# Copy_of_ESP32.net
KiCad netlist of a schematic drawn in Altium Designer
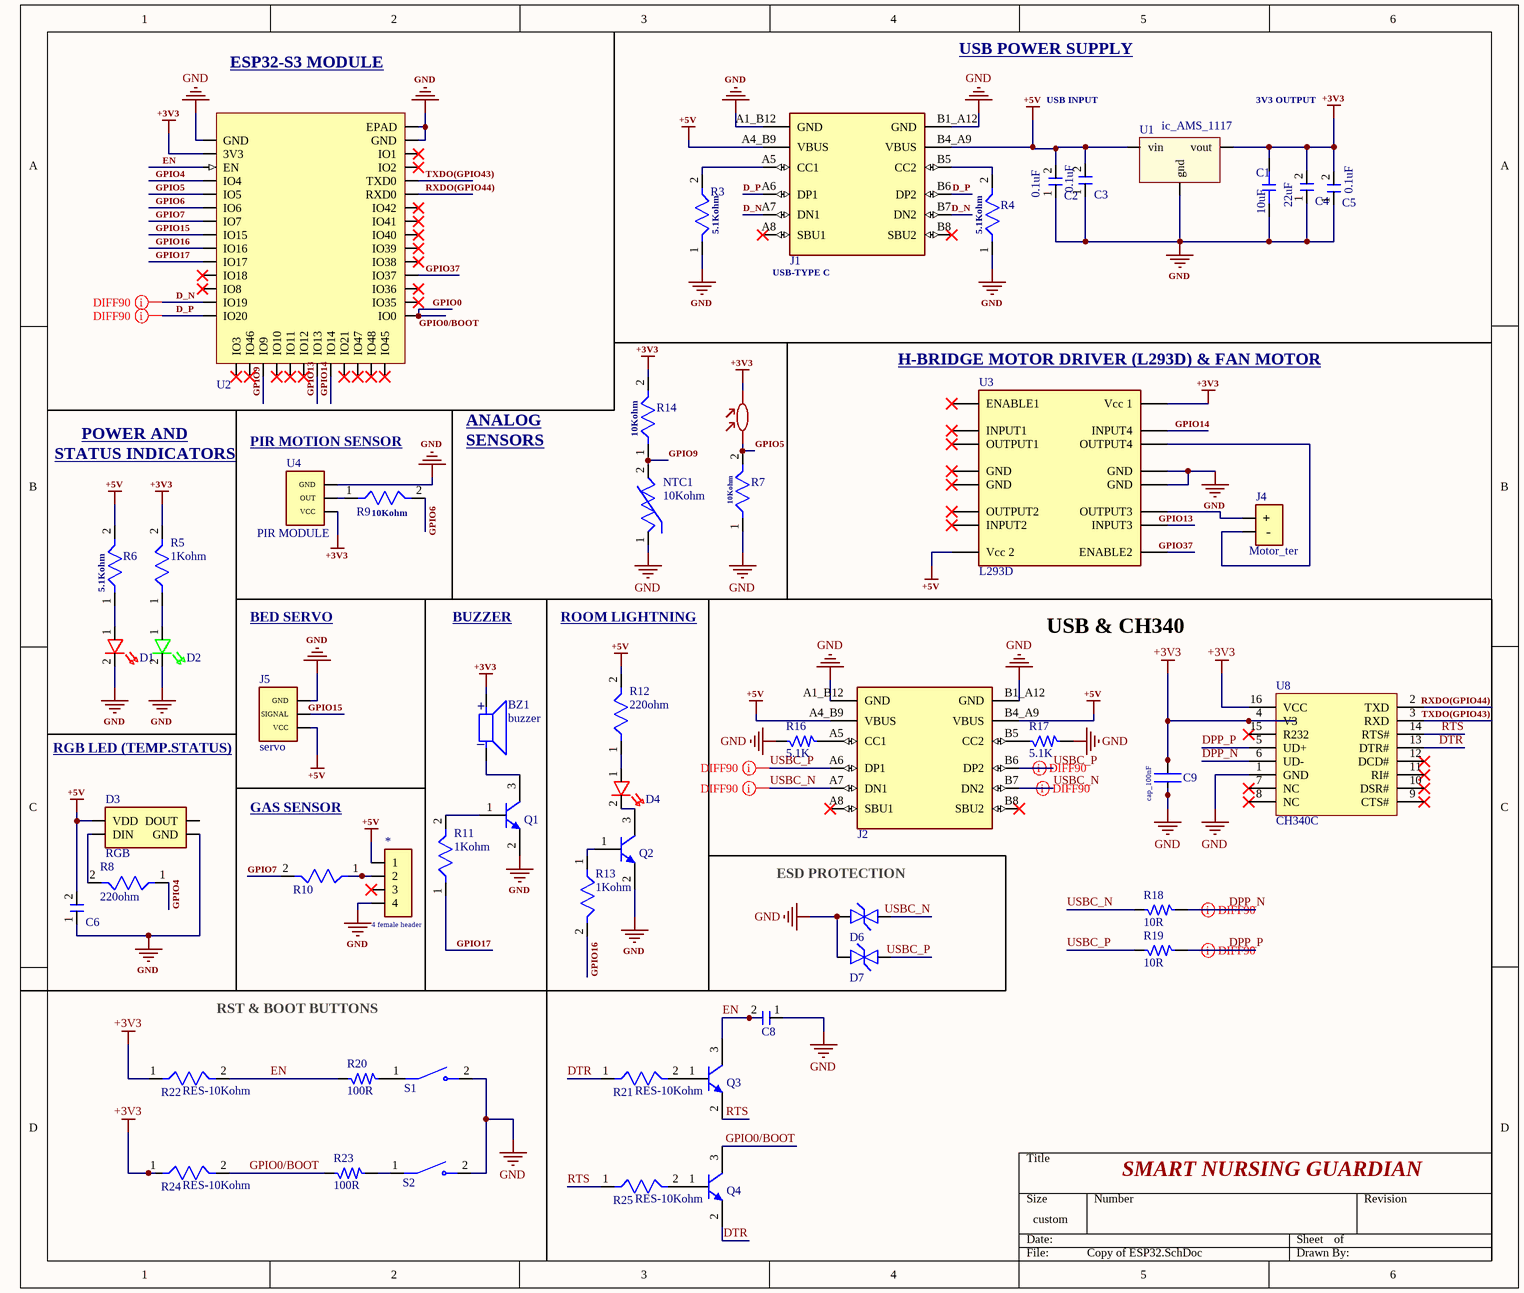
[diagram p0: Copy of ESP32.SchDoc]

(export (version "E")
  (design (tool "Eeschema 10.0.6"))
  (components
    (comp (ref "*")
      (value "4 female header")
      (footprint "4 female header")
      (description "CONN SOCKET 4POS 2.54mm SINGLE ROW TH")
      (fields (field (name "MFR") "BOOMELE(Boom Precision Elec)") (field (name "MPN") "2.54-1*4P"))
      (libsource (lib "mind") (part "4 female header"))
    )
    (comp (ref "BZ1")
      (value "buzzer")
      (footprint "buzzer")
      (description "BUZZER MAGNETIC 4V~8V 12mm TH")
      (fields (field (name "MFR") "Huaneng") (field (name "MPN") "TMB12A05"))
      (libsource (lib "ESP32") (part "buzzer"))
    )
    (comp (ref "C1")
      (value "10uF")
      (footprint "cap_0805")
      (fields (field (name "MFR") "Samsung Electro-Mechanics"))
      (libsource (lib "ESP32") (part "Cap_10uF"))
    )
    (comp (ref "C2")
      (value "0.1uF")
      (footprint "CAPC1608X50N")
      (description "CAP CER 100nF 50V X7R 0603")
      (libsource (lib "ESP32") (part "CAP-0.1uF"))
    )
    (comp (ref "C3")
      (value "0.1uF")
      (footprint "CAPC1608X50N")
      (description "CAP CER 100nF 50V X7R 0603")
      (libsource (lib "ESP32") (part "CAP-0.1uF"))
    )
    (comp (ref "C4")
      (value "22uF")
      (footprint "CAPC2012X125N")
      (description "CAP CER 22uF 25V X5R 0805")
      (libsource (lib "ESP32") (part "CAP-22uF"))
    )
    (comp (ref "C5")
      (value "0.1uF")
      (footprint "CAPC1608X50N")
      (description "CAP CER 100nF 50V X7R 0603")
      (libsource (lib "ESP32") (part "CAP-0.1uF"))
    )
    (comp (ref "C6")
      (value "CAP-0.1uF")
      (footprint "CAPC1608X50N")
      (description "CAP CER 100nF 50V X7R 0603")
      (libsource (lib "ESP32") (part "CAP-0.1uF"))
    )
    (comp (ref "C8")
      (value "CAP-0.1uF")
      (footprint "CAPC1608X50N")
      (description "CAP CER 100nF 50V X7R 0603")
      (libsource (lib "ESP32") (part "CAP-0.1uF"))
    )
    (comp (ref "C9")
      (value "cap_100nF")
      (footprint "CAPC100nf")
      (description "CAP CER 100nF 50V X7R 0805")
      (fields (field (name "MFR") "Samsung Electro-Mechanics") (field (name "MPN") "CL21B104KBCNNNC"))
      (libsource (lib "components") (part "cap_100nF"))
    )
    (comp (ref "D1")
      (value "RED LED")
      (footprint "RED LED")
      (description "LED RED 0603 SMD")
      (fields (field (name "MPN") "YLED0603B"))
      (libsource (lib "ESP32") (part "RED LED"))
    )
    (comp (ref "D2")
      (value "GREEN LED")
      (footprint "RED LED")
      (description "LED GREEN WATER CLEAR 0603 SMD")
      (fields (field (name "MPN") "PSC-1608U52GC-G4"))
      (libsource (lib "ESP32") (part "GREEN LED"))
    )
    (comp (ref "D3")
      (value "RGB")
      (footprint "RGB_LED")
      (fields
        (field (name "MFR") "Shenzhen LED Color Optoelectronic Inc.")
        (field (name "MPN") "SMD-4 Shenzhen LED Color Optoelectronic Inc.")
      )
      (libsource (lib "ESP32") (part "RGB"))
    )
    (comp (ref "D4")
      (value "RED LED")
      (footprint "RED LED")
      (description "LED RED 0603 SMD")
      (fields (field (name "MPN") "YLED0603B"))
      (libsource (lib "ESP32") (part "RED LED"))
    )
    (comp (ref "D6")
      (value "D_TVS_BI_0603")
      (footprint "D_0603")
      (description "Diode TVS / ESD Bidirectional 0603")
      (libsource (lib "components") (part "D_TVS_BI_0603"))
    )
    (comp (ref "D7")
      (value "D_TVS_BI_0603")
      (footprint "D_0603")
      (description "Diode TVS / ESD Bidirectional 0603")
      (fields
        (field (name "MANUFACTURER") "Nexperia")
        (field (name "MANUFACTURER PART NUMBER") "PTVS20VZ1USKYL")
      )
      (libsource (lib "components") (part "D_TVS_BI_0603"))
    )
    (comp (ref "J1")
      (value "USB-TYPE C")
      (footprint "Korean Hroparts Elec TYPE-C-31-M-12")
      (description "CONN RCPT Type-C 16POS SMD")
      (fields (field (name "MPN") "TYPE-C-31-M-12"))
      (libsource (lib "ESP32") (part "USB-TYPE C"))
    )
    (comp (ref "J2")
      (value "USB-TYPE C")
      (footprint "Korean Hroparts Elec TYPE-C-31-M-12")
      (description "CONN RCPT Type-C 16POS SMD")
      (fields (field (name "MPN") "TYPE-C-31-M-12"))
      (libsource (lib "ESP32") (part "USB-TYPE C"))
    )
    (comp (ref "J4")
      (value "Motor_ter")
      (footprint "motor_terminal")
      (description "TERM BLK 2POS 2.54mm TH")
      (fields (field (name "MFR") "Molex") (field (name "MPN") "397730002"))
      (libsource (lib "mind") (part "Motor_ter"))
    )
    (comp (ref "J5")
      (value "servo")
      (footprint "3 pin header 100 mils")
      (fields (field (name "MFR") "Harwin") (field (name "MPN") "M20-9990346"))
      (libsource (lib "ESP32") (part "FAN/DC MOTOR"))
    )
    (comp (ref "NTC1")
      (value "10Kohm")
      (footprint "THERM_NTCG203NH103JT1S")
      (description "10kΩ 440uA 3590K ±5% 200mW ±3% 0805 NTC Thermistors RoHS")
      (fields (field (name "MPN") "NTCG203NH103JT1S"))
      (libsource (lib "ESP32") (part "NTCG203NH103JT1S"))
    )
    (comp (ref "Q1")
      (value "MMSS8050-H-TP")
      (footprint "SOT 23-3")
      (description "Bipolar (BJT) Transistor NPN 25V 1.5A 100MHz 625mW Surface Mount SOT-23")
      (fields (field (name "MANUFACTURER") "MCC"))
      (libsource (lib "components") (part "TRNS-NPN_25V-1.5A-SOT23"))
    )
    (comp (ref "Q2")
      (value "MMSS8050-H-TP")
      (footprint "SOT 23-3")
      (description "Bipolar (BJT) Transistor NPN 25V 1.5A 100MHz 625mW Surface Mount SOT-23")
      (fields (field (name "MANUFACTURER") "MCC"))
      (libsource (lib "components") (part "TRNS-NPN_25V-1.5A-SOT23"))
    )
    (comp (ref "Q3")
      (value "MMSS8050-H-TP")
      (footprint "SOT 23-3")
      (description "Bipolar (BJT) Transistor NPN 25V 1.5A 100MHz 625mW Surface Mount SOT-23")
      (fields (field (name "MANUFACTURER") "MCC"))
      (libsource (lib "components") (part "TRNS-NPN_25V-1.5A-SOT23"))
    )
    (comp (ref "Q4")
      (value "MMSS8050-H-TP")
      (footprint "SOT 23-3")
      (description "Bipolar (BJT) Transistor NPN 25V 1.5A 100MHz 625mW Surface Mount SOT-23")
      (fields (field (name "MANUFACTURER") "MCC"))
      (libsource (lib "components") (part "TRNS-NPN_25V-1.5A-SOT23"))
    )
    (comp (ref "R3")
      (value "5.1Kohm")
      (footprint "RES")
      (description "RES 5.1kΩ ±1% 100mW 0603")
      (libsource (lib "") (part "RES-5.1Kohm_1"))
    )
    (comp (ref "R4")
      (value "5.1Kohm")
      (footprint "RES")
      (description "RES 5.1kΩ ±1% 100mW 0603")
      (libsource (lib "ESP32") (part "RES-5.1Kohm"))
    )
    (comp (ref "R5")
      (value "1Kohm")
      (footprint "RES")
      (description "RES 1kΩ ±1% 100mW 0603")
      (fields (field (name "MPN") "FRC0603F1001TS"))
      (libsource (lib "ESP32") (part "RES_1Kohm"))
    )
    (comp (ref "R6")
      (value "5.1Kohm")
      (footprint "RES")
      (description "RES 5.1kΩ ±1% 100mW 0603")
      (libsource (lib "ESP32") (part "RES-5.1Kohm"))
    )
    (comp (ref "R7")
      (value "10Kohm")
      (footprint "RES")
      (description "RES 10kΩ ±1% 100mW 0603")
      (libsource (lib "ESP32") (part "RES-10Kohm"))
    )
    (comp (ref "R8")
      (value "220ohm")
      (footprint "RES")
      (description "RES 220Ω ±1% 100mW 0603")
      (fields (field (name "MPN") "0603WAF2200T5E"))
      (libsource (lib "ESP32") (part "RES_220ohm"))
    )
    (comp (ref "R9")
      (value "10Kohm")
      (footprint "RES")
      (description "RES 10kΩ ±1% 100mW 0603")
      (libsource (lib "ESP32") (part "RES-10Kohm"))
    )
    (comp (ref "R10")
      (value "RES-10Kohm")
      (footprint "RES")
      (description "RES 10kΩ ±1% 100mW 0603")
      (libsource (lib "ESP32") (part "RES-10Kohm"))
    )
    (comp (ref "R11")
      (value "1Kohm")
      (footprint "RES")
      (description "RES 1kΩ ±1% 100mW 0603")
      (fields (field (name "MPN") "FRC0603F1001TS"))
      (libsource (lib "ESP32") (part "RES_1Kohm"))
    )
    (comp (ref "R12")
      (value "220ohm")
      (footprint "RES")
      (description "RES 220Ω ±1% 100mW 0603")
      (fields (field (name "MPN") "0603WAF2200T5E"))
      (libsource (lib "ESP32") (part "RES_220ohm"))
    )
    (comp (ref "R13")
      (value "1Kohm")
      (footprint "RES")
      (description "RES 1kΩ ±1% 100mW 0603")
      (fields (field (name "MPN") "FRC0603F1001TS"))
      (libsource (lib "ESP32") (part "RES_1Kohm"))
    )
    (comp (ref "R14")
      (value "10Kohm")
      (footprint "RES")
      (description "RES 10kΩ ±1% 100mW 0603")
      (libsource (lib "ESP32") (part "RES-10Kohm"))
    )
    (comp (ref "R15")
      (value "gl5539")
      (footprint "XDCR_PDV-P8003")
      (fields (field (name "MANUFACTURER") "森霸") (field (name "MANUFACTURERPART") "GL5539"))
      (libsource (lib "ESP32") (part "gl5539"))
    )
    (comp (ref "R16")
      (value "5.1K")
      (footprint "RES_0603")
      (description "4.7 kOhms ±1% 0.1W, 1/10W Chip Resistor 0603 (1608 Metric) Moisture Resistant Thick Film")
      (fields (field (name "MANUFACTURER") "Walsin") (field (name "MANUFACTURER PART NUMBER") "WR06X4701FTL"))
      (libsource (lib "components") (part "RES_4.7K-0.1W-1%-0603"))
    )
    (comp (ref "R17")
      (value "5.1K")
      (footprint "RES_0603")
      (description "4.7 kOhms ±1% 0.1W, 1/10W Chip Resistor 0603 (1608 Metric) Moisture Resistant Thick Film")
      (fields (field (name "MANUFACTURER") "Walsin") (field (name "MANUFACTURER PART NUMBER") "WR06X4701FTL"))
      (libsource (lib "components") (part "RES_4.7K-0.1W-1%-0603"))
    )
    (comp (ref "R18")
      (value "10R")
      (footprint "RES_0603")
      (fields (field (name "MANUFACTURER") "Walsin") (field (name "MANUFACTURER PART NUMBER") "WR06X10R0FTL"))
      (libsource (lib "components") (part "RES_10R-0.1W-1%-0603"))
    )
    (comp (ref "R19")
      (value "10R")
      (footprint "RES_0603")
      (fields (field (name "MANUFACTURER") "Walsin") (field (name "MANUFACTURER PART NUMBER") "WR06X10R0FTL"))
      (libsource (lib "components") (part "RES_10R-0.1W-1%-0603"))
    )
    (comp (ref "R20")
      (value "100R")
      (footprint "RES_0603")
      (description "100 Ohms ±1% 0.1W, 1/10W Chip Resistor 0603 (1608 Metric) Thick Film")
      (fields (field (name "MANUFACTURER") "Walsin") (field (name "MANUFACTURER PART NUMBER") "WR06X1000FTL"))
      (libsource (lib "components") (part "RES_100R-0.1W-1%-0603"))
    )
    (comp (ref "R21")
      (value "RES-10Kohm")
      (footprint "RES")
      (description "RES 10kΩ ±1% 100mW 0603")
      (libsource (lib "ESP32") (part "RES-10Kohm"))
    )
    (comp (ref "R22")
      (value "RES-10Kohm")
      (footprint "RES")
      (description "RES 10kΩ ±1% 100mW 0603")
      (libsource (lib "ESP32") (part "RES-10Kohm"))
    )
    (comp (ref "R23")
      (value "100R")
      (footprint "RES_0603")
      (description "100 Ohms ±1% 0.1W, 1/10W Chip Resistor 0603 (1608 Metric) Thick Film")
      (fields (field (name "MANUFACTURER") "Walsin") (field (name "MANUFACTURER PART NUMBER") "WR06X1000FTL"))
      (libsource (lib "components") (part "RES_100R-0.1W-1%-0603"))
    )
    (comp (ref "R24")
      (value "RES-10Kohm")
      (footprint "RES")
      (description "RES 10kΩ ±1% 100mW 0603")
      (libsource (lib "ESP32") (part "RES-10Kohm"))
    )
    (comp (ref "R25")
      (value "RES-10Kohm")
      (footprint "RES")
      (description "RES 10kΩ ±1% 100mW 0603")
      (libsource (lib "ESP32") (part "RES-10Kohm"))
    )
    (comp (ref "S1")
      (value "XUNPU TS-1088-AR02016")
      (footprint "XUNPU TS-1088-AR02016")
      (description "SWITCH TACTILE SPST 160gf SMD")
      (fields (field (name "MPN") "TS-1088-AR02016"))
      (libsource (lib "ESP32") (part "XUNPU TS-1088-AR02016"))
    )
    (comp (ref "S2")
      (value "XUNPU TS-1088-AR02016")
      (footprint "XUNPU TS-1088-AR02016")
      (description "SWITCH TACTILE SPST 160gf SMD")
      (fields (field (name "MPN") "TS-1088-AR02016"))
      (libsource (lib "ESP32") (part "XUNPU TS-1088-AR02016"))
    )
    (comp (ref "U1")
      (value "ic_AMS_1117")
      (footprint "ams1117 ic")
      (description "1A Low Dropout (LDO) Regulator")
      (fields (field (name "MFR") "Advanced Monolithic Systems") (field (name "MFR PART #") "AMS1117-3.3"))
      (libsource (lib "components") (part "ic_AMS_1117"))
    )
    (comp (ref "U2")
      (value "ESP32-S3-WROOM-1")
      (footprint "ESP32-S3-WROOM-1")
      (description "2.4 GHz Wi-Fi + Bluetooth + Bluetooth LE module")
      (libsource (lib "ESP32") (part "ESP32-S3-WROOM-1"))
    )
    (comp (ref "U3")
      (value "L293D")
      (footprint "l293D")
      (description "Bipolar Motor Driver - Parallel 16-PowerDIP")
      (fields (field (name "MFR") "ST") (field (name "SUP PART #") "C12340"))
      (libsource (lib "ESP32") (part "L293D"))
    )
    (comp (ref "U4")
      (value "PIR MODULE")
      (footprint "3 pin header 100 mils")
      (fields (field (name "MFR") "Harwin") (field (name "MPN") "M20-9990346"))
      (libsource (lib "ESP32") (part "3 PIN HEADER 100mils pitch"))
    )
    (comp (ref "U8")
      (value "CH340C")
      (footprint "PCBComponent_1")
      (description "USB Bridge, USB to UART USB 2.0 UART Interface")
      (fields (field (name "MANUFACTURER") "Olimex"))
      (libsource (lib "components") (part "IC_CH340C"))
    )
  )
  (nets
    (net (code "1") (name "+3V3") (class "Default")
      (node (ref "BZ1") (pin "P") (pinfunction "P_P") (pintype "passive"))
      (node (ref "C1") (pin "2") (pinfunction "2_2") (pintype "passive"))
      (node (ref "C4") (pin "2") (pinfunction "2_2") (pintype "passive"))
      (node (ref "C5") (pin "2") (pinfunction "2_2") (pintype "passive"))
      (node (ref "C9") (pin "2") (pinfunction "2_2") (pintype "passive"))
      (node (ref "R14") (pin "2") (pinfunction "2_2") (pintype "passive"))
      (node (ref "R15") (pin "2") (pinfunction "2_2") (pintype "passive"))
      (node (ref "R22") (pin "1") (pinfunction "1_1") (pintype "passive"))
      (node (ref "R24") (pin "1") (pinfunction "1_1") (pintype "passive"))
      (node (ref "R5") (pin "2") (pinfunction "2_2") (pintype "passive"))
      (node (ref "U1") (pin "vout") (pinfunction "vout_vout") (pintype "passive"))
      (node (ref "U2") (pin "2") (pinfunction "3V3_2") (pintype "power_in"))
      (node (ref "U3") (pin "16") (pinfunction "Vcc_1_16") (pintype "power_in"))
      (node (ref "U4") (pin "1") (pinfunction "VCC_1") (pintype "passive"))
      (node (ref "U8") (pin "16") (pinfunction "VCC_16") (pintype "passive"))
      (node (ref "U8") (pin "4") (pinfunction "V3_4") (pintype "passive"))
    )
    (net (code "2") (name "+5V") (class "Default")
      (node (ref "*") (pin "1") (pinfunction "1_1") (pintype "passive"))
      (node (ref "C2") (pin "2") (pinfunction "2_2") (pintype "passive"))
      (node (ref "C3") (pin "2") (pinfunction "2_2") (pintype "passive"))
      (node (ref "C6") (pin "2") (pinfunction "2_2") (pintype "passive"))
      (node (ref "D3") (pin "1") (pinfunction "VDD_1") (pintype "power_in"))
      (node (ref "J1") (pin "A4_B9") (pinfunction "VBUS_A4_B9") (pintype "power_in"))
      (node (ref "J1") (pin "B4_A9") (pinfunction "VBUS_B4_A9") (pintype "power_in"))
      (node (ref "J2") (pin "A4_B9") (pinfunction "VBUS_A4_B9") (pintype "power_in"))
      (node (ref "J2") (pin "B4_A9") (pinfunction "VBUS_B4_A9") (pintype "power_in"))
      (node (ref "J5") (pin "1") (pinfunction "VCC_1") (pintype "passive"))
      (node (ref "R12") (pin "2") (pinfunction "2_2") (pintype "passive"))
      (node (ref "R6") (pin "2") (pinfunction "2_2") (pintype "passive"))
      (node (ref "U1") (pin "vin") (pinfunction "vin_vin") (pintype "passive"))
      (node (ref "U3") (pin "8") (pinfunction "Vcc_2_8") (pintype "power_in"))
    )
    (net (code "3") (name "/DPP_N") (class "Default")
      (node (ref "R18") (pin "2") (pinfunction "2_2") (pintype "passive"))
      (node (ref "U8") (pin "6") (pinfunction "UD-_6") (pintype "passive"))
    )
    (net (code "4") (name "/DPP_P") (class "Default")
      (node (ref "R19") (pin "2") (pinfunction "2_2") (pintype "passive"))
      (node (ref "U8") (pin "5") (pinfunction "UD+_5") (pintype "passive"))
    )
    (net (code "5") (name "/DTR") (class "Default")
      (node (ref "Q4") (pin "2") (pinfunction "E_2") (pintype "passive"))
      (node (ref "R21") (pin "1") (pinfunction "1_1") (pintype "passive"))
      (node (ref "U8") (pin "13") (pinfunction "DTR#_13") (pintype "passive"))
    )
    (net (code "6") (name "/D_N") (class "Default")
      (node (ref "J1") (pin "A7") (pinfunction "DN1_A7") (pintype "bidirectional"))
      (node (ref "J1") (pin "B7") (pinfunction "DN2_B7") (pintype "bidirectional"))
      (node (ref "U2") (pin "13") (pinfunction "IO19_13") (pintype "bidirectional"))
    )
    (net (code "7") (name "/D_P") (class "Default")
      (node (ref "J1") (pin "A6") (pinfunction "DP1_A6") (pintype "bidirectional"))
      (node (ref "J1") (pin "B6") (pinfunction "DP2_B6") (pintype "bidirectional"))
      (node (ref "U2") (pin "14") (pinfunction "IO20_14") (pintype "bidirectional"))
    )
    (net (code "8") (name "/EN") (class "Default")
      (node (ref "C8") (pin "2") (pinfunction "2_2") (pintype "passive"))
      (node (ref "Q3") (pin "3") (pinfunction "C_3") (pintype "passive"))
      (node (ref "R20") (pin "1") (pinfunction "1_1") (pintype "passive"))
      (node (ref "R22") (pin "2") (pinfunction "2_2") (pintype "passive"))
      (node (ref "U2") (pin "3") (pinfunction "EN_3") (pintype "input"))
    )
    (net (code "9") (name "/GPIO0") (class "Default")
      (node (ref "Q4") (pin "3") (pinfunction "C_3") (pintype "passive"))
      (node (ref "R23") (pin "1") (pinfunction "1_1") (pintype "passive"))
      (node (ref "R24") (pin "2") (pinfunction "2_2") (pintype "passive"))
      (node (ref "U2") (pin "27") (pinfunction "IO0_27") (pintype "bidirectional"))
    )
    (net (code "10") (name "/GPIO4") (class "Default")
      (node (ref "R8") (pin "1") (pinfunction "1_1") (pintype "passive"))
      (node (ref "U2") (pin "4") (pinfunction "IO4_4") (pintype "bidirectional"))
    )
    (net (code "11") (name "/GPIO5") (class "Default")
      (node (ref "R15") (pin "1") (pinfunction "1_1") (pintype "passive"))
      (node (ref "R7") (pin "2") (pinfunction "2_2") (pintype "passive"))
      (node (ref "U2") (pin "5") (pinfunction "IO5_5") (pintype "bidirectional"))
    )
    (net (code "12") (name "/GPIO6") (class "Default")
      (node (ref "R9") (pin "2") (pinfunction "2_2") (pintype "passive"))
      (node (ref "U2") (pin "6") (pinfunction "IO6_6") (pintype "bidirectional"))
    )
    (net (code "13") (name "/GPIO7") (class "Default")
      (node (ref "R10") (pin "2") (pinfunction "2_2") (pintype "passive"))
      (node (ref "U2") (pin "7") (pinfunction "IO7_7") (pintype "bidirectional"))
    )
    (net (code "14") (name "/GPIO9") (class "Default")
      (node (ref "NTC1") (pin "2") (pinfunction "2_2") (pintype "passive"))
      (node (ref "R14") (pin "1") (pinfunction "1_1") (pintype "passive"))
      (node (ref "U2") (pin "17") (pinfunction "IO9_17") (pintype "bidirectional"))
    )
    (net (code "15") (name "/GPIO13") (class "Default")
      (node (ref "U2") (pin "21") (pinfunction "IO13_21") (pintype "bidirectional"))
      (node (ref "U3") (pin "10") (pinfunction "INPUT3_10") (pintype "passive"))
    )
    (net (code "16") (name "/GPIO14") (class "Default")
      (node (ref "U2") (pin "22") (pinfunction "IO14_22") (pintype "bidirectional"))
      (node (ref "U3") (pin "15") (pinfunction "INPUT4_15") (pintype "passive"))
    )
    (net (code "17") (name "/GPIO15") (class "Default")
      (node (ref "J5") (pin "2") (pinfunction "SIGNAL_2") (pintype "passive"))
      (node (ref "U2") (pin "8") (pinfunction "IO15_8") (pintype "bidirectional"))
    )
    (net (code "18") (name "/GPIO16") (class "Default")
      (node (ref "R13") (pin "2") (pinfunction "2_2") (pintype "passive"))
      (node (ref "U2") (pin "9") (pinfunction "IO16_9") (pintype "bidirectional"))
    )
    (net (code "19") (name "/GPIO17") (class "Default")
      (node (ref "R11") (pin "1") (pinfunction "1_1") (pintype "passive"))
      (node (ref "U2") (pin "10") (pinfunction "IO17_10") (pintype "bidirectional"))
    )
    (net (code "20") (name "/GPIO37") (class "Default")
      (node (ref "U2") (pin "30") (pinfunction "IO37_30") (pintype "bidirectional"))
      (node (ref "U3") (pin "9") (pinfunction "ENABLE2_9") (pintype "passive"))
    )
    (net (code "21") (name "/RTS") (class "Default")
      (node (ref "Q3") (pin "2") (pinfunction "E_2") (pintype "passive"))
      (node (ref "R25") (pin "1") (pinfunction "1_1") (pintype "passive"))
      (node (ref "U8") (pin "14") (pinfunction "RTS#_14") (pintype "passive"))
    )
    (net (code "22") (name "/RXDO(GPIO44)") (class "Default")
      (node (ref "U2") (pin "36") (pinfunction "RXD0_36") (pintype "bidirectional"))
      (node (ref "U8") (pin "2") (pinfunction "TXD_2") (pintype "passive"))
    )
    (net (code "23") (name "/TXDO(GPIO43)") (class "Default")
      (node (ref "U2") (pin "37") (pinfunction "TXD0_37") (pintype "bidirectional"))
      (node (ref "U8") (pin "3") (pinfunction "RXD_3") (pintype "passive"))
    )
    (net (code "24") (name "/USBC_N") (class "Default")
      (node (ref "D6") (pin "K") (pinfunction "K_K") (pintype "passive"))
      (node (ref "J2") (pin "A7") (pinfunction "DN1_A7") (pintype "bidirectional"))
      (node (ref "J2") (pin "B7") (pinfunction "DN2_B7") (pintype "bidirectional"))
      (node (ref "R18") (pin "1") (pinfunction "1_1") (pintype "passive"))
    )
    (net (code "25") (name "/USBC_P") (class "Default")
      (node (ref "D7") (pin "K") (pinfunction "K_K") (pintype "passive"))
      (node (ref "J2") (pin "A6") (pinfunction "DP1_A6") (pintype "bidirectional"))
      (node (ref "J2") (pin "B6") (pinfunction "DP2_B6") (pintype "bidirectional"))
      (node (ref "R19") (pin "1") (pinfunction "1_1") (pintype "passive"))
    )
    (net (code "26") (name "GND") (class "Default")
      (node (ref "*") (pin "4") (pinfunction "4_4") (pintype "passive"))
      (node (ref "C1") (pin "1") (pinfunction "1_1") (pintype "passive"))
      (node (ref "C2") (pin "1") (pinfunction "1_1") (pintype "passive"))
      (node (ref "C3") (pin "1") (pinfunction "1_1") (pintype "passive"))
      (node (ref "C4") (pin "1") (pinfunction "1_1") (pintype "passive"))
      (node (ref "C5") (pin "1") (pinfunction "1_1") (pintype "passive"))
      (node (ref "C6") (pin "1") (pinfunction "1_1") (pintype "passive"))
      (node (ref "C8") (pin "1") (pinfunction "1_1") (pintype "passive"))
      (node (ref "C9") (pin "1") (pinfunction "1_1") (pintype "passive"))
      (node (ref "D1") (pin "2") (pinfunction "2_2") (pintype "passive"))
      (node (ref "D2") (pin "2") (pinfunction "2_2") (pintype "passive"))
      (node (ref "D3") (pin "3") (pinfunction "GND_3") (pintype "power_in"))
      (node (ref "D6") (pin "A") (pinfunction "A_A") (pintype "passive"))
      (node (ref "D7") (pin "A") (pinfunction "A_A") (pintype "passive"))
      (node (ref "J1") (pin "A1_B12") (pinfunction "GND_A1_B12") (pintype "power_in"))
      (node (ref "J1") (pin "B1_A12") (pinfunction "GND_B1_A12") (pintype "power_in"))
      (node (ref "J2") (pin "A1_B12") (pinfunction "GND_A1_B12") (pintype "power_in"))
      (node (ref "J2") (pin "B1_A12") (pinfunction "GND_B1_A12") (pintype "power_in"))
      (node (ref "J5") (pin "3") (pinfunction "GND_3") (pintype "passive"))
      (node (ref "NTC1") (pin "1") (pinfunction "1_1") (pintype "passive"))
      (node (ref "Q1") (pin "2") (pinfunction "E_2") (pintype "passive"))
      (node (ref "Q2") (pin "2") (pinfunction "E_2") (pintype "passive"))
      (node (ref "R16") (pin "1") (pinfunction "1_1") (pintype "passive"))
      (node (ref "R17") (pin "2") (pinfunction "2_2") (pintype "passive"))
      (node (ref "R3") (pin "1") (pinfunction "1_1") (pintype "passive"))
      (node (ref "R4") (pin "1") (pinfunction "1_1") (pintype "passive"))
      (node (ref "R7") (pin "1") (pinfunction "1_1") (pintype "passive"))
      (node (ref "S1") (pin "2") (pinfunction "2_2") (pintype "passive"))
      (node (ref "S2") (pin "2") (pinfunction "2_2") (pintype "passive"))
      (node (ref "U1") (pin "gnd") (pinfunction "gnd_gnd") (pintype "passive"))
      (node (ref "U2") (pin "1") (pinfunction "GND_1") (pintype "power_in"))
      (node (ref "U2") (pin "40") (pinfunction "GND_40") (pintype "power_in"))
      (node (ref "U2") (pin "41") (pinfunction "EPAD_41") (pintype "power_in"))
      (node (ref "U3") (pin "12") (pinfunction "GND_12") (pintype "power_in"))
      (node (ref "U3") (pin "13") (pinfunction "GND_13") (pintype "power_in"))
      (node (ref "U4") (pin "3") (pinfunction "GND_3") (pintype "passive"))
      (node (ref "U8") (pin "1") (pinfunction "GND_1") (pintype "passive"))
    )
    (net (code "27") (name "Net-(*-Pad2)") (class "Default")
      (node (ref "*") (pin "2") (pinfunction "2_2") (pintype "passive"))
      (node (ref "R10") (pin "1") (pinfunction "1_1") (pintype "passive"))
    )
    (net (code "28") (name "Net-(D1-Pad1)") (class "Default")
      (node (ref "D1") (pin "1") (pinfunction "1_1") (pintype "passive"))
      (node (ref "R6") (pin "1") (pinfunction "1_1") (pintype "passive"))
    )
    (net (code "29") (name "Net-(D2-Pad1)") (class "Default")
      (node (ref "D2") (pin "1") (pinfunction "1_1") (pintype "passive"))
      (node (ref "R5") (pin "1") (pinfunction "1_1") (pintype "passive"))
    )
    (net (code "30") (name "Net-(D3-DIN)") (class "Default")
      (node (ref "D3") (pin "2") (pinfunction "DIN_2") (pintype "passive"))
      (node (ref "R8") (pin "2") (pinfunction "2_2") (pintype "passive"))
    )
    (net (code "31") (name "Net-(D4-Pad1)") (class "Default")
      (node (ref "D4") (pin "1") (pinfunction "1_1") (pintype "passive"))
      (node (ref "R12") (pin "1") (pinfunction "1_1") (pintype "passive"))
    )
    (net (code "32") (name "Net-(J1-CC1)") (class "Default")
      (node (ref "J1") (pin "A5") (pinfunction "CC1_A5") (pintype "bidirectional"))
      (node (ref "R3") (pin "2") (pinfunction "2_2") (pintype "passive"))
    )
    (net (code "33") (name "Net-(J1-CC2)") (class "Default")
      (node (ref "J1") (pin "B5") (pinfunction "CC2_B5") (pintype "bidirectional"))
      (node (ref "R4") (pin "2") (pinfunction "2_2") (pintype "passive"))
    )
    (net (code "34") (name "Net-(J2-CC1)") (class "Default")
      (node (ref "J2") (pin "A5") (pinfunction "CC1_A5") (pintype "bidirectional"))
      (node (ref "R16") (pin "2") (pinfunction "2_2") (pintype "passive"))
    )
    (net (code "35") (name "Net-(J2-CC2)") (class "Default")
      (node (ref "J2") (pin "B5") (pinfunction "CC2_B5") (pintype "bidirectional"))
      (node (ref "R17") (pin "1") (pinfunction "1_1") (pintype "passive"))
    )
    (net (code "36") (name "Net-(J4-+)") (class "Default")
      (node (ref "J4") (pin "1") (pinfunction "+_1") (pintype "passive"))
      (node (ref "U3") (pin "11") (pinfunction "OUTPUT3_11") (pintype "passive"))
    )
    (net (code "37") (name "Net-(J4--)") (class "Default")
      (node (ref "J4") (pin "2") (pinfunction "-_2") (pintype "passive"))
      (node (ref "U3") (pin "14") (pinfunction "OUTPUT4_14") (pintype "passive"))
    )
    (net (code "38") (name "Net-(Q1-B)") (class "Default")
      (node (ref "Q1") (pin "1") (pinfunction "B_1") (pintype "passive"))
      (node (ref "R11") (pin "2") (pinfunction "2_2") (pintype "passive"))
    )
    (net (code "39") (name "Net-(Q1-C)") (class "Default")
      (node (ref "BZ1") (pin "N") (pinfunction "N_N") (pintype "passive"))
      (node (ref "Q1") (pin "3") (pinfunction "C_3") (pintype "passive"))
    )
    (net (code "40") (name "Net-(Q2-B)") (class "Default")
      (node (ref "Q2") (pin "1") (pinfunction "B_1") (pintype "passive"))
      (node (ref "R13") (pin "1") (pinfunction "1_1") (pintype "passive"))
    )
    (net (code "41") (name "Net-(Q2-C)") (class "Default")
      (node (ref "D4") (pin "2") (pinfunction "2_2") (pintype "passive"))
      (node (ref "Q2") (pin "3") (pinfunction "C_3") (pintype "passive"))
    )
    (net (code "42") (name "Net-(Q3-B)") (class "Default")
      (node (ref "Q3") (pin "1") (pinfunction "B_1") (pintype "passive"))
      (node (ref "R21") (pin "2") (pinfunction "2_2") (pintype "passive"))
    )
    (net (code "43") (name "Net-(Q4-B)") (class "Default")
      (node (ref "Q4") (pin "1") (pinfunction "B_1") (pintype "passive"))
      (node (ref "R25") (pin "2") (pinfunction "2_2") (pintype "passive"))
    )
    (net (code "44") (name "Net-(R20-Pad2)") (class "Default")
      (node (ref "R20") (pin "2") (pinfunction "2_2") (pintype "passive"))
      (node (ref "S1") (pin "1") (pinfunction "1_1") (pintype "passive"))
    )
    (net (code "45") (name "Net-(R23-Pad2)") (class "Default")
      (node (ref "R23") (pin "2") (pinfunction "2_2") (pintype "passive"))
      (node (ref "S2") (pin "1") (pinfunction "1_1") (pintype "passive"))
    )
    (net (code "46") (name "Net-(U4-OUT)") (class "Default")
      (node (ref "R9") (pin "1") (pinfunction "1_1") (pintype "passive"))
      (node (ref "U4") (pin "2") (pinfunction "OUT_2") (pintype "passive"))
    )
    (net (code "47") (name "unconnected-(*-Pad3)") (class "Default")
      (node (ref "*") (pin "3") (pinfunction "3_3") (pintype "passive+no_connect"))
    )
    (net (code "48") (name "unconnected-(D3-DOUT-Pad4)") (class "Default")
      (node (ref "D3") (pin "4") (pinfunction "DOUT_4") (pintype "passive"))
    )
    (net (code "49") (name "unconnected-(J1-SBU1-PadA8)") (class "Default")
      (node (ref "J1") (pin "A8") (pinfunction "SBU1_A8") (pintype "bidirectional+no_connect"))
    )
    (net (code "50") (name "unconnected-(J1-SBU2-PadB8)") (class "Default")
      (node (ref "J1") (pin "B8") (pinfunction "SBU2_B8") (pintype "bidirectional+no_connect"))
    )
    (net (code "51") (name "unconnected-(J2-SBU1-PadA8)") (class "Default")
      (node (ref "J2") (pin "A8") (pinfunction "SBU1_A8") (pintype "bidirectional+no_connect"))
    )
    (net (code "52") (name "unconnected-(J2-SBU2-PadB8)") (class "Default")
      (node (ref "J2") (pin "B8") (pinfunction "SBU2_B8") (pintype "bidirectional+no_connect"))
    )
    (net (code "53") (name "unconnected-(U2-IO1-Pad39)") (class "Default")
      (node (ref "U2") (pin "39") (pinfunction "IO1_39") (pintype "bidirectional+no_connect"))
    )
    (net (code "54") (name "unconnected-(U2-IO2-Pad38)") (class "Default")
      (node (ref "U2") (pin "38") (pinfunction "IO2_38") (pintype "bidirectional+no_connect"))
    )
    (net (code "55") (name "unconnected-(U2-IO3-Pad15)") (class "Default")
      (node (ref "U2") (pin "15") (pinfunction "IO3_15") (pintype "bidirectional+no_connect"))
    )
    (net (code "56") (name "unconnected-(U2-IO8-Pad12)") (class "Default")
      (node (ref "U2") (pin "12") (pinfunction "IO8_12") (pintype "bidirectional+no_connect"))
    )
    (net (code "57") (name "unconnected-(U2-IO10-Pad18)") (class "Default")
      (node (ref "U2") (pin "18") (pinfunction "IO10_18") (pintype "bidirectional+no_connect"))
    )
    (net (code "58") (name "unconnected-(U2-IO11-Pad19)") (class "Default")
      (node (ref "U2") (pin "19") (pinfunction "IO11_19") (pintype "bidirectional+no_connect"))
    )
    (net (code "59") (name "unconnected-(U2-IO12-Pad20)") (class "Default")
      (node (ref "U2") (pin "20") (pinfunction "IO12_20") (pintype "bidirectional+no_connect"))
    )
    (net (code "60") (name "unconnected-(U2-IO18-Pad11)") (class "Default")
      (node (ref "U2") (pin "11") (pinfunction "IO18_11") (pintype "bidirectional+no_connect"))
    )
    (net (code "61") (name "unconnected-(U2-IO21-Pad23)") (class "Default")
      (node (ref "U2") (pin "23") (pinfunction "IO21_23") (pintype "bidirectional+no_connect"))
    )
    (net (code "62") (name "unconnected-(U2-IO35-Pad28)") (class "Default")
      (node (ref "U2") (pin "28") (pinfunction "IO35_28") (pintype "bidirectional+no_connect"))
    )
    (net (code "63") (name "unconnected-(U2-IO36-Pad29)") (class "Default")
      (node (ref "U2") (pin "29") (pinfunction "IO36_29") (pintype "bidirectional+no_connect"))
    )
    (net (code "64") (name "unconnected-(U2-IO38-Pad31)") (class "Default")
      (node (ref "U2") (pin "31") (pinfunction "IO38_31") (pintype "bidirectional+no_connect"))
    )
    (net (code "65") (name "unconnected-(U2-IO39-Pad32)") (class "Default")
      (node (ref "U2") (pin "32") (pinfunction "IO39_32") (pintype "bidirectional+no_connect"))
    )
    (net (code "66") (name "unconnected-(U2-IO40-Pad33)") (class "Default")
      (node (ref "U2") (pin "33") (pinfunction "IO40_33") (pintype "bidirectional+no_connect"))
    )
    (net (code "67") (name "unconnected-(U2-IO41-Pad34)") (class "Default")
      (node (ref "U2") (pin "34") (pinfunction "IO41_34") (pintype "bidirectional+no_connect"))
    )
    (net (code "68") (name "unconnected-(U2-IO42-Pad35)") (class "Default")
      (node (ref "U2") (pin "35") (pinfunction "IO42_35") (pintype "bidirectional+no_connect"))
    )
    (net (code "69") (name "unconnected-(U2-IO45-Pad26)") (class "Default")
      (node (ref "U2") (pin "26") (pinfunction "IO45_26") (pintype "bidirectional+no_connect"))
    )
    (net (code "70") (name "unconnected-(U2-IO46-Pad16)") (class "Default")
      (node (ref "U2") (pin "16") (pinfunction "IO46_16") (pintype "bidirectional+no_connect"))
    )
    (net (code "71") (name "unconnected-(U2-IO47-Pad24)") (class "Default")
      (node (ref "U2") (pin "24") (pinfunction "IO47_24") (pintype "bidirectional+no_connect"))
    )
    (net (code "72") (name "unconnected-(U2-IO48-Pad25)") (class "Default")
      (node (ref "U2") (pin "25") (pinfunction "IO48_25") (pintype "bidirectional+no_connect"))
    )
    (net (code "73") (name "unconnected-(U3-ENABLE1-Pad1)") (class "Default")
      (node (ref "U3") (pin "1") (pinfunction "ENABLE1_1") (pintype "passive+no_connect"))
    )
    (net (code "74") (name "unconnected-(U3-GND-Pad4)") (class "Default")
      (node (ref "U3") (pin "4") (pinfunction "GND_4") (pintype "power_in+no_connect"))
    )
    (net (code "75") (name "unconnected-(U3-GND-Pad5)") (class "Default")
      (node (ref "U3") (pin "5") (pinfunction "GND_5") (pintype "power_in+no_connect"))
    )
    (net (code "76") (name "unconnected-(U3-INPUT1-Pad2)") (class "Default")
      (node (ref "U3") (pin "2") (pinfunction "INPUT1_2") (pintype "passive+no_connect"))
    )
    (net (code "77") (name "unconnected-(U3-INPUT2-Pad7)") (class "Default")
      (node (ref "U3") (pin "7") (pinfunction "INPUT2_7") (pintype "passive+no_connect"))
    )
    (net (code "78") (name "unconnected-(U3-OUTPUT1-Pad3)") (class "Default")
      (node (ref "U3") (pin "3") (pinfunction "OUTPUT1_3") (pintype "passive+no_connect"))
    )
    (net (code "79") (name "unconnected-(U3-OUTPUT2-Pad6)") (class "Default")
      (node (ref "U3") (pin "6") (pinfunction "OUTPUT2_6") (pintype "passive+no_connect"))
    )
    (net (code "80") (name "unconnected-(U8-CTS#-Pad9)") (class "Default")
      (node (ref "U8") (pin "9") (pinfunction "CTS#_9") (pintype "passive+no_connect"))
    )
    (net (code "81") (name "unconnected-(U8-DCD#-Pad12)") (class "Default")
      (node (ref "U8") (pin "12") (pinfunction "DCD#_12") (pintype "passive+no_connect"))
    )
    (net (code "82") (name "unconnected-(U8-DSR#-Pad10)") (class "Default")
      (node (ref "U8") (pin "10") (pinfunction "DSR#_10") (pintype "passive+no_connect"))
    )
    (net (code "83") (name "unconnected-(U8-NC-Pad7)") (class "Default")
      (node (ref "U8") (pin "7") (pinfunction "NC_7") (pintype "passive+no_connect"))
    )
    (net (code "84") (name "unconnected-(U8-NC-Pad8)") (class "Default")
      (node (ref "U8") (pin "8") (pinfunction "NC_8") (pintype "passive+no_connect"))
    )
    (net (code "85") (name "unconnected-(U8-R232-Pad15)") (class "Default")
      (node (ref "U8") (pin "15") (pinfunction "R232_15") (pintype "passive+no_connect"))
    )
    (net (code "86") (name "unconnected-(U8-RI#-Pad11)") (class "Default")
      (node (ref "U8") (pin "11") (pinfunction "RI#_11") (pintype "passive+no_connect"))
    )
  )
)
